# sch.net
KiCad netlist of a schematic drawn in Altium Designer
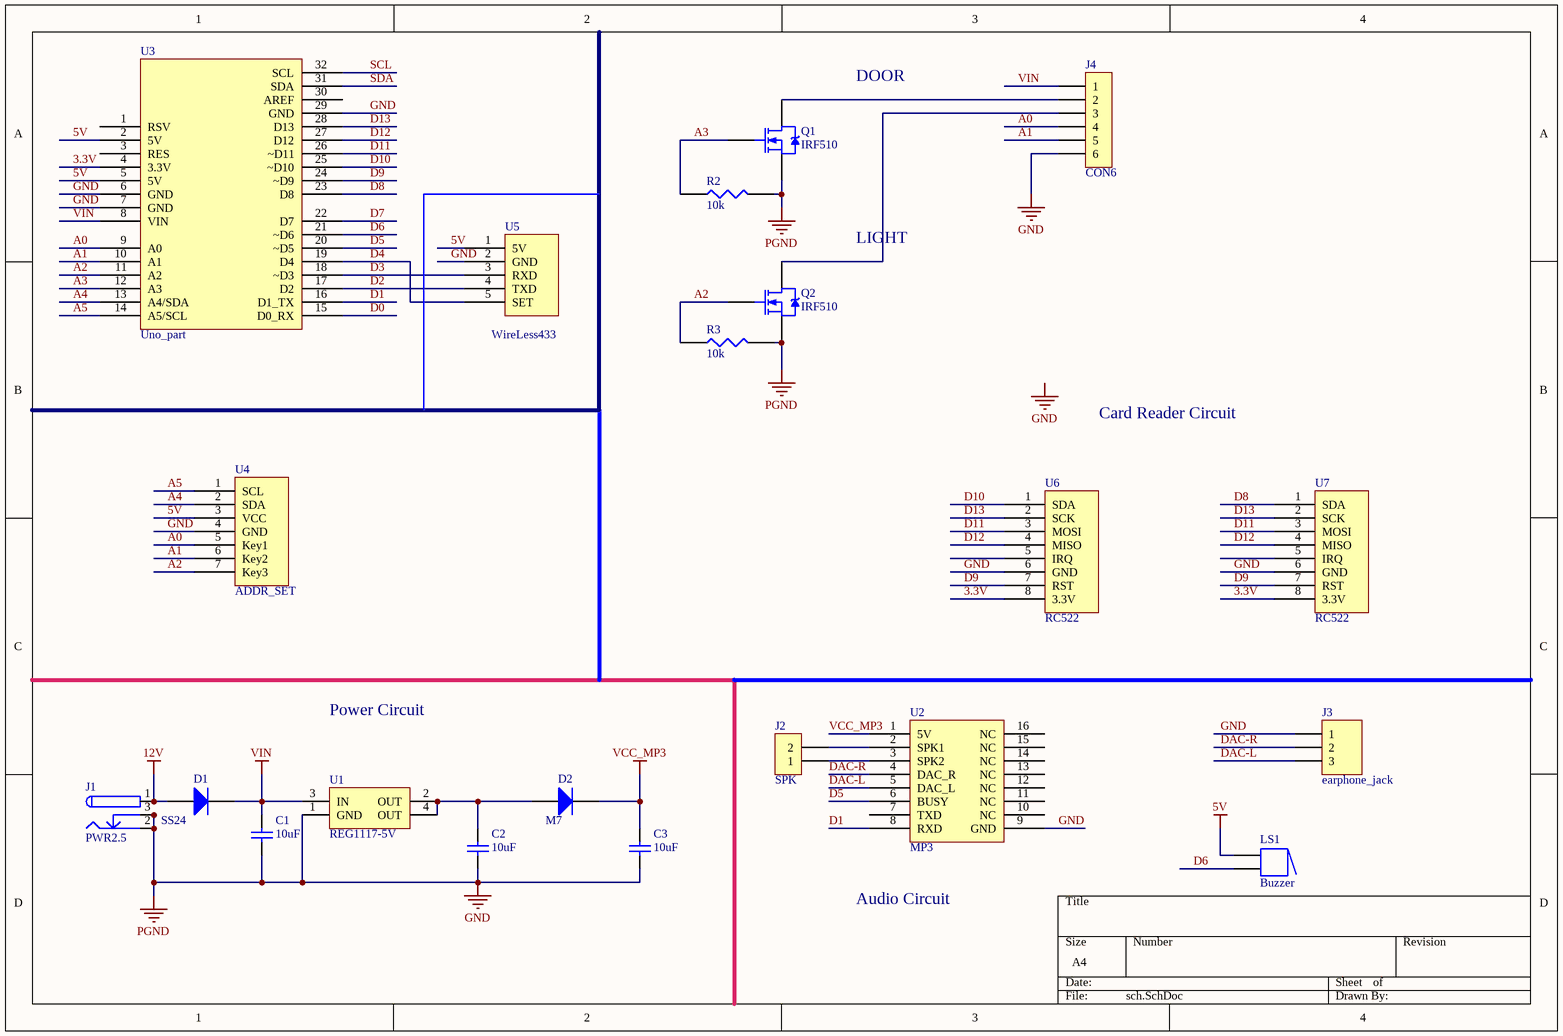
[diagram p0: sch.SchDoc]

(export (version "E")
  (design (tool "Eeschema 10.0.6"))
  (components
    (comp (ref "C1")
      (value "10uF")
      (footprint "1206")
      (description "Capacitor (Semiconductor SIM Model)")
      (fields (field (name "Comment") "Cap Semi") (field (name "PUBLISHER") "Altium Limited"))
      (libsource (lib "Miscellaneous Devices") (part "Cap Semi"))
    )
    (comp (ref "C2")
      (value "10uF")
      (footprint "1206")
      (description "Capacitor (Semiconductor SIM Model)")
      (fields (field (name "Comment") "Cap Semi") (field (name "PUBLISHER") "Altium Limited"))
      (libsource (lib "Miscellaneous Devices") (part "Cap Semi"))
    )
    (comp (ref "C3")
      (value "10uF")
      (footprint "1206")
      (description "Capacitor (Semiconductor SIM Model)")
      (fields (field (name "Comment") "Cap Semi") (field (name "PUBLISHER") "Altium Limited"))
      (libsource (lib "Miscellaneous Devices") (part "Cap Semi"))
    )
    (comp (ref "D1")
      (value "SS24")
      (footprint "SMB")
      (description "1 Amp General Purpose Rectifier")
      (fields (field (name "PUBLISHER") "Altium Limited"))
      (libsource (lib "Miscellaneous Devices") (part "Diode 1N4001"))
    )
    (comp (ref "D2")
      (value "M7")
      (footprint "SMA")
      (description "1 Amp General Purpose Rectifier")
      (fields (field (name "PUBLISHER") "Altium Limited"))
      (libsource (lib "Miscellaneous Devices") (part "Diode 1N4001"))
    )
    (comp (ref "J1")
      (value "PWR2.5")
      (footprint "KLD-0202_new")
      (description "Low Voltage Power Supply Connector")
      (fields (field (name "PUBLISHER") "Altium Limited"))
      (libsource (lib "Miscellaneous Connectors") (part "PWR2.5"))
    )
    (comp (ref "J2") (value "SPK") (footprint "DG1282") (libsource (lib "常用元件库") (part "CON2")))
    (comp (ref "J3")
      (value "earphone_jack")
      (footprint "PcbLib1:Phone-Jack")
      (description "Header, 3-Pin")
      (fields (field (name "PUBLISHER") "Altium Limited"))
      (libsource (lib "Miscellaneous Connectors") (part "Header 3"))
    )
    (comp (ref "J4")
      (value "CON6")
      (footprint "PcbLib1:POWER CONN6")
      (description "Connector")
      (libsource (lib "Miscellaneous Devices") (part "CON6"))
    )
    (comp (ref "LS1")
      (value "Buzzer")
      (footprint "BUZZ")
      (description "Magnetic Transducer Buzzer")
      (fields (field (name "PUBLISHER") "Altium Limited"))
      (libsource (lib "Miscellaneous Devices") (part "Buzzer"))
    )
    (comp (ref "Q1")
      (value "IRF510")
      (footprint "常用元件封装:TO-220")
      (description "HEXFET N-Channel Power MOSFET")
      (fields (field (name "PUBLISHER") "Altium Limited"))
      (libsource (lib "IR Discrete MOSFET - Power") (part "IRF510"))
    )
    (comp (ref "Q2")
      (value "IRF510")
      (footprint "常用元件封装:TO-220")
      (description "HEXFET N-Channel Power MOSFET")
      (fields (field (name "PUBLISHER") "Altium Limited"))
      (libsource (lib "IR Discrete MOSFET - Power") (part "IRF510"))
    )
    (comp (ref "R2") (value "10k") (footprint "1206") (libsource (lib "Miscellaneous Devices") (part "RES1")))
    (comp (ref "R3") (value "10k") (footprint "1206") (libsource (lib "Miscellaneous Devices") (part "RES1")))
    (comp (ref "U1")
      (value "REG1117-5V")
      (footprint "SOT223")
      (description "800mA and 1A Low Dropout Positive Regulator 2.85V, 3.3V, 5V, and Adjustable")
      (fields (field (name "PUBLISHER") "Altium Limited"))
      (libsource (lib "BB Power Mgt Voltage Regulator") (part "REG1117-2.85"))
    )
    (comp (ref "U2") (value "MP3") (footprint "MP3") (libsource (lib "Schlib") (part "MP3")))
    (comp (ref "U3") (value "Uno_part") (footprint "UNO") (libsource (lib "Schlib") (part "Uno_part")))
    (comp (ref "U4")
      (value "ADDR_SET")
      (footprint "Miscellaneous Connectors:HDR1X7")
      (libsource (lib "Schlib") (part "ADDR_SET"))
    )
    (comp (ref "U5")
      (value "WireLess433")
      (footprint "Miscellaneous Connectors:HDR1X5")
      (libsource (lib "Schlib") (part "WireLess433"))
    )
    (comp (ref "U6")
      (value "RC522")
      (footprint "Miscellaneous Connectors:HDR1X8")
      (libsource (lib "Schlib") (part "RC522"))
    )
    (comp (ref "U7") (value "RC522") (footprint "HDR1X8") (libsource (lib "Schlib") (part "RC522")))
  )
  (nets
    (net (code "1") (name "/3.3V") (class "Default")
      (node (ref "U3") (pin "4") (pinfunction "3.3V_4") (pintype "passive"))
      (node (ref "U6") (pin "8") (pinfunction "3.3V_8") (pintype "passive"))
      (node (ref "U7") (pin "8") (pinfunction "3.3V_8") (pintype "passive"))
    )
    (net (code "2") (name "/A0") (class "Default")
      (node (ref "J4") (pin "4") (pinfunction "4_4") (pintype "passive"))
      (node (ref "U3") (pin "9") (pinfunction "A0_9") (pintype "passive"))
      (node (ref "U4") (pin "5") (pinfunction "Key1_5") (pintype "passive"))
    )
    (net (code "3") (name "/A1") (class "Default")
      (node (ref "J4") (pin "5") (pinfunction "5_5") (pintype "passive"))
      (node (ref "U3") (pin "10") (pinfunction "A1_10") (pintype "passive"))
      (node (ref "U4") (pin "6") (pinfunction "Key2_6") (pintype "passive"))
    )
    (net (code "4") (name "/A2") (class "Default")
      (node (ref "Q2") (pin "1") (pinfunction "G_1") (pintype "passive"))
      (node (ref "R3") (pin "1") (pinfunction "1_1") (pintype "passive"))
      (node (ref "U3") (pin "11") (pinfunction "A2_11") (pintype "passive"))
      (node (ref "U4") (pin "7") (pinfunction "Key3_7") (pintype "passive"))
    )
    (net (code "5") (name "/A3") (class "Default")
      (node (ref "Q1") (pin "1") (pinfunction "G_1") (pintype "passive"))
      (node (ref "R2") (pin "1") (pinfunction "1_1") (pintype "passive"))
      (node (ref "U3") (pin "12") (pinfunction "A3_12") (pintype "passive"))
    )
    (net (code "6") (name "/A4") (class "Default")
      (node (ref "U3") (pin "13") (pinfunction "A4/SDA_13") (pintype "passive"))
      (node (ref "U4") (pin "2") (pinfunction "SDA_2") (pintype "passive"))
    )
    (net (code "7") (name "/A5") (class "Default")
      (node (ref "U3") (pin "14") (pinfunction "A5/SCL_14") (pintype "passive"))
      (node (ref "U4") (pin "1") (pinfunction "SCL_1") (pintype "passive"))
    )
    (net (code "8") (name "/D0") (class "Default")
      (node (ref "U3") (pin "15") (pinfunction "D0_RX_15") (pintype "passive"))
    )
    (net (code "9") (name "/D1") (class "Default")
      (node (ref "U2") (pin "8") (pinfunction "RXD_8") (pintype "passive"))
      (node (ref "U3") (pin "16") (pinfunction "D1_TX_16") (pintype "passive"))
    )
    (net (code "10") (name "/D2") (class "Default")
      (node (ref "U3") (pin "17") (pinfunction "D2_17") (pintype "passive"))
      (node (ref "U5") (pin "4") (pinfunction "TXD_4") (pintype "passive"))
    )
    (net (code "11") (name "/D3") (class "Default")
      (node (ref "U3") (pin "18") (pinfunction "~D3_18") (pintype "passive"))
      (node (ref "U5") (pin "3") (pinfunction "RXD_3") (pintype "passive"))
    )
    (net (code "12") (name "/D4") (class "Default")
      (node (ref "U3") (pin "19") (pinfunction "D4_19") (pintype "passive"))
      (node (ref "U5") (pin "5") (pinfunction "SET_5") (pintype "passive"))
    )
    (net (code "13") (name "/D5") (class "Default")
      (node (ref "U2") (pin "6") (pinfunction "BUSY_6") (pintype "passive"))
      (node (ref "U3") (pin "20") (pinfunction "~D5_20") (pintype "passive"))
    )
    (net (code "14") (name "/D6") (class "Default")
      (node (ref "LS1") (pin "2") (pinfunction "2_2") (pintype "passive"))
      (node (ref "U3") (pin "21") (pinfunction "~D6_21") (pintype "passive"))
    )
    (net (code "15") (name "/D7") (class "Default")
      (node (ref "U3") (pin "22") (pinfunction "D7_22") (pintype "passive"))
    )
    (net (code "16") (name "/D8") (class "Default")
      (node (ref "U3") (pin "23") (pinfunction "D8_23") (pintype "passive"))
      (node (ref "U7") (pin "1") (pinfunction "SDA_1") (pintype "passive"))
    )
    (net (code "17") (name "/D9") (class "Default")
      (node (ref "U3") (pin "24") (pinfunction "~D9_24") (pintype "passive"))
      (node (ref "U6") (pin "7") (pinfunction "RST_7") (pintype "passive"))
      (node (ref "U7") (pin "7") (pinfunction "RST_7") (pintype "passive"))
    )
    (net (code "18") (name "/D10") (class "Default")
      (node (ref "U3") (pin "25") (pinfunction "~D10_25") (pintype "passive"))
      (node (ref "U6") (pin "1") (pinfunction "SDA_1") (pintype "passive"))
    )
    (net (code "19") (name "/D11") (class "Default")
      (node (ref "U3") (pin "26") (pinfunction "~D11_26") (pintype "passive"))
      (node (ref "U6") (pin "3") (pinfunction "MOSI_3") (pintype "passive"))
      (node (ref "U7") (pin "3") (pinfunction "MOSI_3") (pintype "passive"))
    )
    (net (code "20") (name "/D12") (class "Default")
      (node (ref "U3") (pin "27") (pinfunction "D12_27") (pintype "passive"))
      (node (ref "U6") (pin "4") (pinfunction "MISO_4") (pintype "passive"))
      (node (ref "U7") (pin "4") (pinfunction "MISO_4") (pintype "passive"))
    )
    (net (code "21") (name "/D13") (class "Default")
      (node (ref "U3") (pin "28") (pinfunction "D13_28") (pintype "passive"))
      (node (ref "U6") (pin "2") (pinfunction "SCK_2") (pintype "passive"))
      (node (ref "U7") (pin "2") (pinfunction "SCK_2") (pintype "passive"))
    )
    (net (code "22") (name "/DAC-L") (class "Default")
      (node (ref "J3") (pin "3") (pinfunction "3_3") (pintype "passive"))
      (node (ref "U2") (pin "5") (pinfunction "DAC_L_5") (pintype "passive"))
    )
    (net (code "23") (name "/DAC-R") (class "Default")
      (node (ref "J3") (pin "2") (pinfunction "2_2") (pintype "passive"))
      (node (ref "U2") (pin "4") (pinfunction "DAC_R_4") (pintype "passive"))
    )
    (net (code "24") (name "/SCL") (class "Default")
      (node (ref "U3") (pin "32") (pinfunction "SCL_32") (pintype "passive"))
    )
    (net (code "25") (name "/SDA") (class "Default")
      (node (ref "U3") (pin "31") (pinfunction "SDA_31") (pintype "passive"))
    )
    (net (code "26") (name "5V") (class "Default")
      (node (ref "LS1") (pin "1") (pinfunction "1_1") (pintype "passive"))
      (node (ref "U3") (pin "2") (pinfunction "5V_2") (pintype "passive"))
      (node (ref "U3") (pin "5") (pinfunction "5V_5") (pintype "passive"))
      (node (ref "U4") (pin "3") (pinfunction "VCC_3") (pintype "passive"))
      (node (ref "U5") (pin "1") (pinfunction "5V_1") (pintype "passive"))
    )
    (net (code "27") (name "12V") (class "Default")
      (node (ref "D1") (pin "A") (pinfunction "A_A") (pintype "passive"))
      (node (ref "J1") (pin "1") (pinfunction "1_1") (pintype "power_in"))
      (node (ref "J1") (pin "1A") (pinfunction "1A_1A") (pintype "power_in"))
      (node (ref "J1") (pin "1B") (pinfunction "1B_1B") (pintype "power_in"))
    )
    (net (code "28") (name "GND") (class "Default")
      (node (ref "C1") (pin "1") (pinfunction "1_1") (pintype "passive"))
      (node (ref "C2") (pin "1") (pinfunction "1_1") (pintype "passive"))
      (node (ref "C3") (pin "1") (pinfunction "1_1") (pintype "passive"))
      (node (ref "J1") (pin "2") (pinfunction "2_2") (pintype "power_in"))
      (node (ref "J1") (pin "2A") (pinfunction "2A_2A") (pintype "power_in"))
      (node (ref "J1") (pin "2B") (pinfunction "2B_2B") (pintype "power_in"))
      (node (ref "J1") (pin "3") (pinfunction "3_3") (pintype "power_in"))
      (node (ref "J1") (pin "3A") (pinfunction "3A_3A") (pintype "power_in"))
      (node (ref "J1") (pin "3B") (pinfunction "3B_3B") (pintype "power_in"))
      (node (ref "J3") (pin "1") (pinfunction "1_1") (pintype "passive"))
      (node (ref "J4") (pin "6") (pinfunction "6_6") (pintype "passive"))
      (node (ref "Q1") (pin "3") (pinfunction "S_3") (pintype "passive"))
      (node (ref "Q2") (pin "3") (pinfunction "S_3") (pintype "passive"))
      (node (ref "R2") (pin "2") (pinfunction "2_2") (pintype "passive"))
      (node (ref "R3") (pin "2") (pinfunction "2_2") (pintype "passive"))
      (node (ref "U1") (pin "1") (pinfunction "GND_1") (pintype "power_in"))
      (node (ref "U2") (pin "9") (pinfunction "GND_9") (pintype "passive"))
      (node (ref "U3") (pin "29") (pinfunction "GND_29") (pintype "passive"))
      (node (ref "U3") (pin "6") (pinfunction "GND_6") (pintype "passive"))
      (node (ref "U3") (pin "7") (pinfunction "GND_7") (pintype "passive"))
      (node (ref "U4") (pin "4") (pinfunction "GND_4") (pintype "passive"))
      (node (ref "U5") (pin "2") (pinfunction "GND_2") (pintype "passive"))
      (node (ref "U6") (pin "6") (pinfunction "GND_6") (pintype "passive"))
      (node (ref "U7") (pin "6") (pinfunction "GND_6") (pintype "passive"))
    )
    (net (code "29") (name "Net-(C2-Pad2)") (class "Default")
      (node (ref "C2") (pin "2") (pinfunction "2_2") (pintype "passive"))
      (node (ref "D2") (pin "A") (pinfunction "A_A") (pintype "passive"))
      (node (ref "U1") (pin "2") (pinfunction "OUT_2") (pintype "power_in"))
      (node (ref "U1") (pin "4") (pinfunction "OUT_4") (pintype "power_in"))
    )
    (net (code "30") (name "Net-(Q1-D)") (class "Default")
      (node (ref "J4") (pin "2") (pinfunction "2_2") (pintype "passive"))
      (node (ref "Q1") (pin "2") (pinfunction "D_2") (pintype "passive"))
    )
    (net (code "31") (name "Net-(Q2-D)") (class "Default")
      (node (ref "J4") (pin "3") (pinfunction "3_3") (pintype "passive"))
      (node (ref "Q2") (pin "2") (pinfunction "D_2") (pintype "passive"))
    )
    (net (code "32") (name "Net-(U2-SPK1)") (class "Default")
      (node (ref "J2") (pin "2") (pinfunction "2_2") (pintype "passive"))
      (node (ref "U2") (pin "2") (pinfunction "SPK1_2") (pintype "passive"))
    )
    (net (code "33") (name "Net-(U2-SPK2)") (class "Default")
      (node (ref "J2") (pin "1") (pinfunction "1_1") (pintype "passive"))
      (node (ref "U2") (pin "3") (pinfunction "SPK2_3") (pintype "passive"))
    )
    (net (code "34") (name "VCC_MP3") (class "Default")
      (node (ref "C3") (pin "2") (pinfunction "2_2") (pintype "passive"))
      (node (ref "D2") (pin "K") (pinfunction "K_K") (pintype "passive"))
      (node (ref "U2") (pin "1") (pinfunction "5V_1") (pintype "passive"))
    )
    (net (code "35") (name "VIN") (class "Default")
      (node (ref "C1") (pin "2") (pinfunction "2_2") (pintype "passive"))
      (node (ref "D1") (pin "K") (pinfunction "K_K") (pintype "passive"))
      (node (ref "J4") (pin "1") (pinfunction "1_1") (pintype "passive"))
      (node (ref "U1") (pin "3") (pinfunction "IN_3") (pintype "power_in"))
      (node (ref "U3") (pin "8") (pinfunction "VIN_8") (pintype "passive"))
    )
    (net (code "36") (name "unconnected-(U2-NC-Pad10)") (class "Default")
      (node (ref "U2") (pin "10") (pinfunction "NC_10") (pintype "passive"))
    )
    (net (code "37") (name "unconnected-(U2-NC-Pad11)") (class "Default")
      (node (ref "U2") (pin "11") (pinfunction "NC_11") (pintype "passive"))
    )
    (net (code "38") (name "unconnected-(U2-NC-Pad12)") (class "Default")
      (node (ref "U2") (pin "12") (pinfunction "NC_12") (pintype "passive"))
    )
    (net (code "39") (name "unconnected-(U2-NC-Pad13)") (class "Default")
      (node (ref "U2") (pin "13") (pinfunction "NC_13") (pintype "passive"))
    )
    (net (code "40") (name "unconnected-(U2-NC-Pad14)") (class "Default")
      (node (ref "U2") (pin "14") (pinfunction "NC_14") (pintype "passive"))
    )
    (net (code "41") (name "unconnected-(U2-NC-Pad15)") (class "Default")
      (node (ref "U2") (pin "15") (pinfunction "NC_15") (pintype "passive"))
    )
    (net (code "42") (name "unconnected-(U2-NC-Pad16)") (class "Default")
      (node (ref "U2") (pin "16") (pinfunction "NC_16") (pintype "passive"))
    )
    (net (code "43") (name "unconnected-(U2-TXD-Pad7)") (class "Default")
      (node (ref "U2") (pin "7") (pinfunction "TXD_7") (pintype "passive"))
    )
    (net (code "44") (name "unconnected-(U3-AREF-Pad30)") (class "Default")
      (node (ref "U3") (pin "30") (pinfunction "AREF_30") (pintype "passive"))
    )
    (net (code "45") (name "unconnected-(U3-RES-Pad3)") (class "Default")
      (node (ref "U3") (pin "3") (pinfunction "RES_3") (pintype "passive"))
    )
    (net (code "46") (name "unconnected-(U3-RSV-Pad1)") (class "Default")
      (node (ref "U3") (pin "1") (pinfunction "RSV_1") (pintype "passive"))
    )
    (net (code "47") (name "unconnected-(U6-IRQ-Pad5)") (class "Default")
      (node (ref "U6") (pin "5") (pinfunction "IRQ_5") (pintype "passive"))
    )
    (net (code "48") (name "unconnected-(U7-IRQ-Pad5)") (class "Default")
      (node (ref "U7") (pin "5") (pinfunction "IRQ_5") (pintype "passive"))
    )
  )
)
